# watering_unit.net
KiCad netlist of a schematic drawn in EAGLE
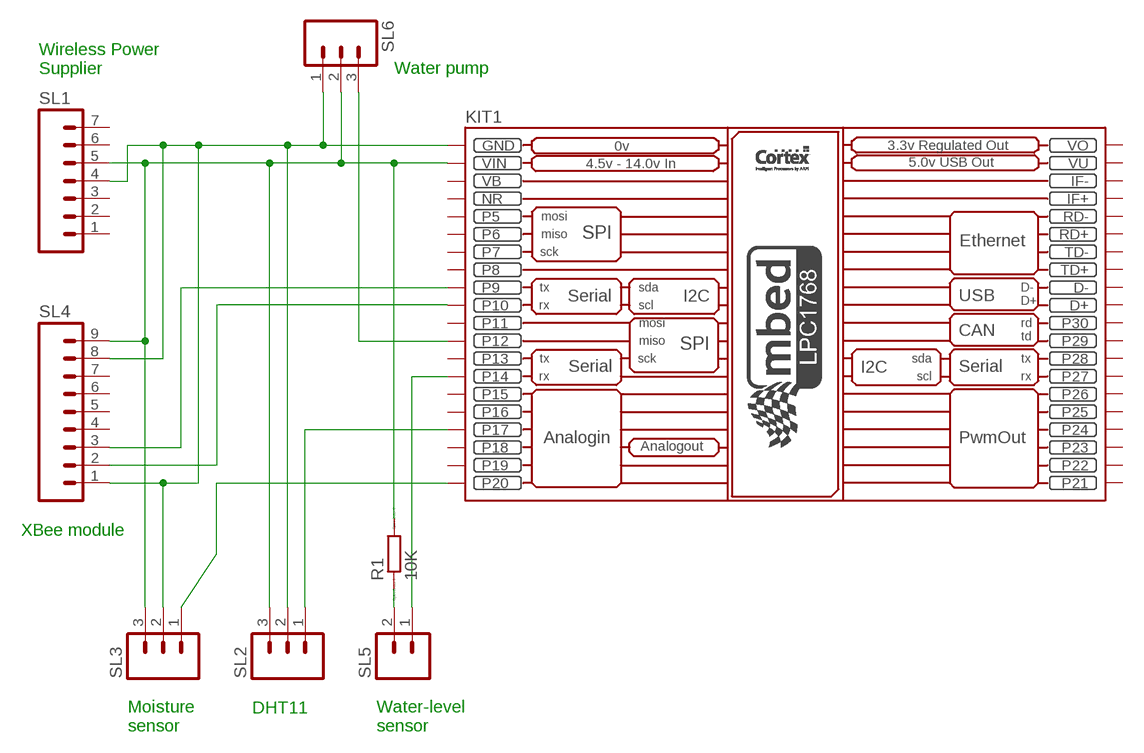
[diagram p0: schematic, sheet 1]

(export (version "E")
  (design (tool "Eeschema 10.0.6"))
  (components
    (comp (ref "KIT1")
      (value "MBED_NXP_LPC1768")
      (footprint "eagle-import:MBED-KIT")
      (libsource (lib "eagle-import") (part "MBED_NXP_LPC1768"))
    )
    (comp (ref "R1")
      (value "10K")
      (footprint "eagle-import:0204_7")
      (libsource (lib "eagle-import") (part "R0204/7"))
    )
    (comp (ref "SL1")
      (value "M07")
      (footprint "eagle-import:07P")
      (libsource (lib "eagle-import") (part "M07"))
    )
    (comp (ref "SL2")
      (value "M03")
      (footprint "eagle-import:03P")
      (libsource (lib "eagle-import") (part "M03"))
    )
    (comp (ref "SL3")
      (value "M03")
      (footprint "eagle-import:03P")
      (libsource (lib "eagle-import") (part "M03"))
    )
    (comp (ref "SL4")
      (value "M09")
      (footprint "eagle-import:09P")
      (libsource (lib "eagle-import") (part "M09"))
    )
    (comp (ref "SL5")
      (value "M02")
      (footprint "eagle-import:02P")
      (libsource (lib "eagle-import") (part "M02"))
    )
    (comp (ref "SL6")
      (value "M03")
      (footprint "eagle-import:03P")
      (libsource (lib "eagle-import") (part "M03"))
    )
  )
  (nets
    (net (code "1") (name "/NR") (class "Default")
      (node (ref "KIT1") (pin "NR") (pinfunction "NR_NR") (pintype "power_in"))
    )
    (net (code "2") (name "/VB") (class "Default")
      (node (ref "KIT1") (pin "VB") (pinfunction "VB_VB") (pintype "power_in"))
    )
    (net (code "3") (name "/VO") (class "Default")
      (node (ref "KIT1") (pin "VOUT") (pinfunction "VO_VOUT") (pintype "power_in"))
    )
    (net (code "4") (name "/VU") (class "Default")
      (node (ref "KIT1") (pin "VU") (pinfunction "VU_VU") (pintype "power_in"))
    )
    (net (code "5") (name "Net-(KIT1-P9)") (class "Default")
      (node (ref "KIT1") (pin "P$9") (pinfunction "P9_P$9") (pintype "bidirectional"))
      (node (ref "SL4") (pin "3") (pinfunction "3_3") (pintype "passive"))
    )
    (net (code "6") (name "Net-(KIT1-P10)") (class "Default")
      (node (ref "KIT1") (pin "P$10") (pinfunction "P10_P$10") (pintype "bidirectional"))
      (node (ref "SL4") (pin "2") (pinfunction "2_2") (pintype "passive"))
    )
    (net (code "7") (name "Net-(KIT1-P12)") (class "Default")
      (node (ref "KIT1") (pin "P$12") (pinfunction "P12_P$12") (pintype "bidirectional"))
      (node (ref "SL6") (pin "3") (pinfunction "3_3") (pintype "passive"))
    )
    (net (code "8") (name "Net-(KIT1-P14)") (class "Default")
      (node (ref "KIT1") (pin "P$14") (pinfunction "P14_P$14") (pintype "bidirectional"))
      (node (ref "SL5") (pin "1") (pinfunction "1_1") (pintype "passive"))
    )
    (net (code "9") (name "Net-(KIT1-P17)") (class "Default")
      (node (ref "KIT1") (pin "P$17") (pinfunction "P17_P$17") (pintype "bidirectional"))
      (node (ref "SL2") (pin "1") (pinfunction "1_1") (pintype "passive"))
    )
    (net (code "10") (name "Net-(KIT1-P20)") (class "Default")
      (node (ref "KIT1") (pin "P$20") (pinfunction "P20_P$20") (pintype "bidirectional"))
      (node (ref "SL3") (pin "1") (pinfunction "1_1") (pintype "passive"))
    )
    (net (code "11") (name "Net-(KIT1-PadGND)") (class "Default")
      (node (ref "KIT1") (pin "GND") (pinfunction "GND_GND") (pintype "power_in"))
      (node (ref "SL1") (pin "4") (pinfunction "4_4") (pintype "passive"))
      (node (ref "SL2") (pin "2") (pinfunction "2_2") (pintype "passive"))
      (node (ref "SL3") (pin "2") (pinfunction "2_2") (pintype "passive"))
      (node (ref "SL4") (pin "1") (pinfunction "1_1") (pintype "passive"))
      (node (ref "SL4") (pin "8") (pinfunction "8_8") (pintype "passive"))
      (node (ref "SL6") (pin "1") (pinfunction "1_1") (pintype "passive"))
    )
    (net (code "12") (name "Net-(KIT1-PadVIN)") (class "Default")
      (node (ref "KIT1") (pin "VIN") (pinfunction "VIN_VIN") (pintype "power_in"))
      (node (ref "R1") (pin "2") (pinfunction "2_2") (pintype "passive"))
      (node (ref "SL1") (pin "5") (pinfunction "5_5") (pintype "passive"))
      (node (ref "SL2") (pin "3") (pinfunction "3_3") (pintype "passive"))
      (node (ref "SL3") (pin "3") (pinfunction "3_3") (pintype "passive"))
      (node (ref "SL4") (pin "9") (pinfunction "9_9") (pintype "passive"))
      (node (ref "SL6") (pin "2") (pinfunction "2_2") (pintype "passive"))
    )
    (net (code "13") (name "Net-(R1-Pad1)") (class "Default")
      (node (ref "R1") (pin "1") (pinfunction "1_1") (pintype "passive"))
      (node (ref "SL5") (pin "2") (pinfunction "2_2") (pintype "passive"))
    )
    (net (code "14") (name "unconnected-(KIT1-P5-PadP$5)") (class "Default")
      (node (ref "KIT1") (pin "P$5") (pinfunction "P5_P$5") (pintype "bidirectional"))
    )
    (net (code "15") (name "unconnected-(KIT1-P6-PadP$6)") (class "Default")
      (node (ref "KIT1") (pin "P$6") (pinfunction "P6_P$6") (pintype "bidirectional"))
    )
    (net (code "16") (name "unconnected-(KIT1-P7-PadP$7)") (class "Default")
      (node (ref "KIT1") (pin "P$7") (pinfunction "P7_P$7") (pintype "bidirectional"))
    )
    (net (code "17") (name "unconnected-(KIT1-P8-PadP$8)") (class "Default")
      (node (ref "KIT1") (pin "P$8") (pinfunction "P8_P$8") (pintype "bidirectional"))
    )
    (net (code "18") (name "unconnected-(KIT1-P11-PadP$11)") (class "Default")
      (node (ref "KIT1") (pin "P$11") (pinfunction "P11_P$11") (pintype "bidirectional"))
    )
    (net (code "19") (name "unconnected-(KIT1-P13-PadP$13)") (class "Default")
      (node (ref "KIT1") (pin "P$13") (pinfunction "P13_P$13") (pintype "bidirectional"))
    )
    (net (code "20") (name "unconnected-(KIT1-P15-PadP$15)") (class "Default")
      (node (ref "KIT1") (pin "P$15") (pinfunction "P15_P$15") (pintype "bidirectional"))
    )
    (net (code "21") (name "unconnected-(KIT1-P16-PadP$16)") (class "Default")
      (node (ref "KIT1") (pin "P$16") (pinfunction "P16_P$16") (pintype "bidirectional"))
    )
    (net (code "22") (name "unconnected-(KIT1-P18-PadP$18)") (class "Default")
      (node (ref "KIT1") (pin "P$18") (pinfunction "P18_P$18") (pintype "bidirectional"))
    )
    (net (code "23") (name "unconnected-(KIT1-P19-PadP$19)") (class "Default")
      (node (ref "KIT1") (pin "P$19") (pinfunction "P19_P$19") (pintype "bidirectional"))
    )
    (net (code "24") (name "unconnected-(KIT1-P21-PadP$21)") (class "Default")
      (node (ref "KIT1") (pin "P$21") (pinfunction "P21_P$21") (pintype "bidirectional"))
    )
    (net (code "25") (name "unconnected-(KIT1-P22-PadP$22)") (class "Default")
      (node (ref "KIT1") (pin "P$22") (pinfunction "P22_P$22") (pintype "bidirectional"))
    )
    (net (code "26") (name "unconnected-(KIT1-P23-PadP$23)") (class "Default")
      (node (ref "KIT1") (pin "P$23") (pinfunction "P23_P$23") (pintype "bidirectional"))
    )
    (net (code "27") (name "unconnected-(KIT1-P24-PadP$24)") (class "Default")
      (node (ref "KIT1") (pin "P$24") (pinfunction "P24_P$24") (pintype "bidirectional"))
    )
    (net (code "28") (name "unconnected-(KIT1-P25-PadP$25)") (class "Default")
      (node (ref "KIT1") (pin "P$25") (pinfunction "P25_P$25") (pintype "bidirectional"))
    )
    (net (code "29") (name "unconnected-(KIT1-P26-PadP$26)") (class "Default")
      (node (ref "KIT1") (pin "P$26") (pinfunction "P26_P$26") (pintype "bidirectional"))
    )
    (net (code "30") (name "unconnected-(KIT1-P27-PadP$27)") (class "Default")
      (node (ref "KIT1") (pin "P$27") (pinfunction "P27_P$27") (pintype "bidirectional"))
    )
    (net (code "31") (name "unconnected-(KIT1-P28-PadP$28)") (class "Default")
      (node (ref "KIT1") (pin "P$28") (pinfunction "P28_P$28") (pintype "bidirectional"))
    )
    (net (code "32") (name "unconnected-(KIT1-P29-PadP$29)") (class "Default")
      (node (ref "KIT1") (pin "P$29") (pinfunction "P29_P$29") (pintype "bidirectional"))
    )
    (net (code "33") (name "unconnected-(KIT1-P30-PadP$30)") (class "Default")
      (node (ref "KIT1") (pin "P$30") (pinfunction "P30_P$30") (pintype "bidirectional"))
    )
    (net (code "34") (name "unconnected-(KIT1-PadD+)") (class "Default")
      (node (ref "KIT1") (pin "D+") (pinfunction "D+_D+") (pintype "bidirectional"))
    )
    (net (code "35") (name "unconnected-(KIT1-PadD-)") (class "Default")
      (node (ref "KIT1") (pin "D-") (pinfunction "D-_D-") (pintype "bidirectional"))
    )
    (net (code "36") (name "unconnected-(KIT1-PadIF+)") (class "Default")
      (node (ref "KIT1") (pin "IF+") (pinfunction "IF+_IF+") (pintype "bidirectional"))
    )
    (net (code "37") (name "unconnected-(KIT1-PadIF-)") (class "Default")
      (node (ref "KIT1") (pin "IF-") (pinfunction "IF-_IF-") (pintype "bidirectional"))
    )
    (net (code "38") (name "unconnected-(KIT1-PadRD+)") (class "Default")
      (node (ref "KIT1") (pin "RD+") (pinfunction "RD+_RD+") (pintype "bidirectional"))
    )
    (net (code "39") (name "unconnected-(KIT1-PadRD-)") (class "Default")
      (node (ref "KIT1") (pin "RD-") (pinfunction "RD-_RD-") (pintype "bidirectional"))
    )
    (net (code "40") (name "unconnected-(KIT1-PadTD+)") (class "Default")
      (node (ref "KIT1") (pin "TD+") (pinfunction "TD+_TD+") (pintype "bidirectional"))
    )
    (net (code "41") (name "unconnected-(KIT1-PadTD-)") (class "Default")
      (node (ref "KIT1") (pin "TD-") (pinfunction "TD-_TD-") (pintype "bidirectional"))
    )
    (net (code "42") (name "unconnected-(SL1-Pad1)") (class "Default")
      (node (ref "SL1") (pin "1") (pinfunction "1_1") (pintype "passive"))
    )
    (net (code "43") (name "unconnected-(SL1-Pad2)") (class "Default")
      (node (ref "SL1") (pin "2") (pinfunction "2_2") (pintype "passive"))
    )
    (net (code "44") (name "unconnected-(SL1-Pad3)") (class "Default")
      (node (ref "SL1") (pin "3") (pinfunction "3_3") (pintype "passive"))
    )
    (net (code "45") (name "unconnected-(SL1-Pad6)") (class "Default")
      (node (ref "SL1") (pin "6") (pinfunction "6_6") (pintype "passive"))
    )
    (net (code "46") (name "unconnected-(SL1-Pad7)") (class "Default")
      (node (ref "SL1") (pin "7") (pinfunction "7_7") (pintype "passive"))
    )
    (net (code "47") (name "unconnected-(SL4-Pad4)") (class "Default")
      (node (ref "SL4") (pin "4") (pinfunction "4_4") (pintype "passive"))
    )
    (net (code "48") (name "unconnected-(SL4-Pad5)") (class "Default")
      (node (ref "SL4") (pin "5") (pinfunction "5_5") (pintype "passive"))
    )
    (net (code "49") (name "unconnected-(SL4-Pad6)") (class "Default")
      (node (ref "SL4") (pin "6") (pinfunction "6_6") (pintype "passive"))
    )
    (net (code "50") (name "unconnected-(SL4-Pad7)") (class "Default")
      (node (ref "SL4") (pin "7") (pinfunction "7_7") (pintype "passive"))
    )
  )
)
